# com.net
KiCad netlist of a schematic drawn in Altium Designer
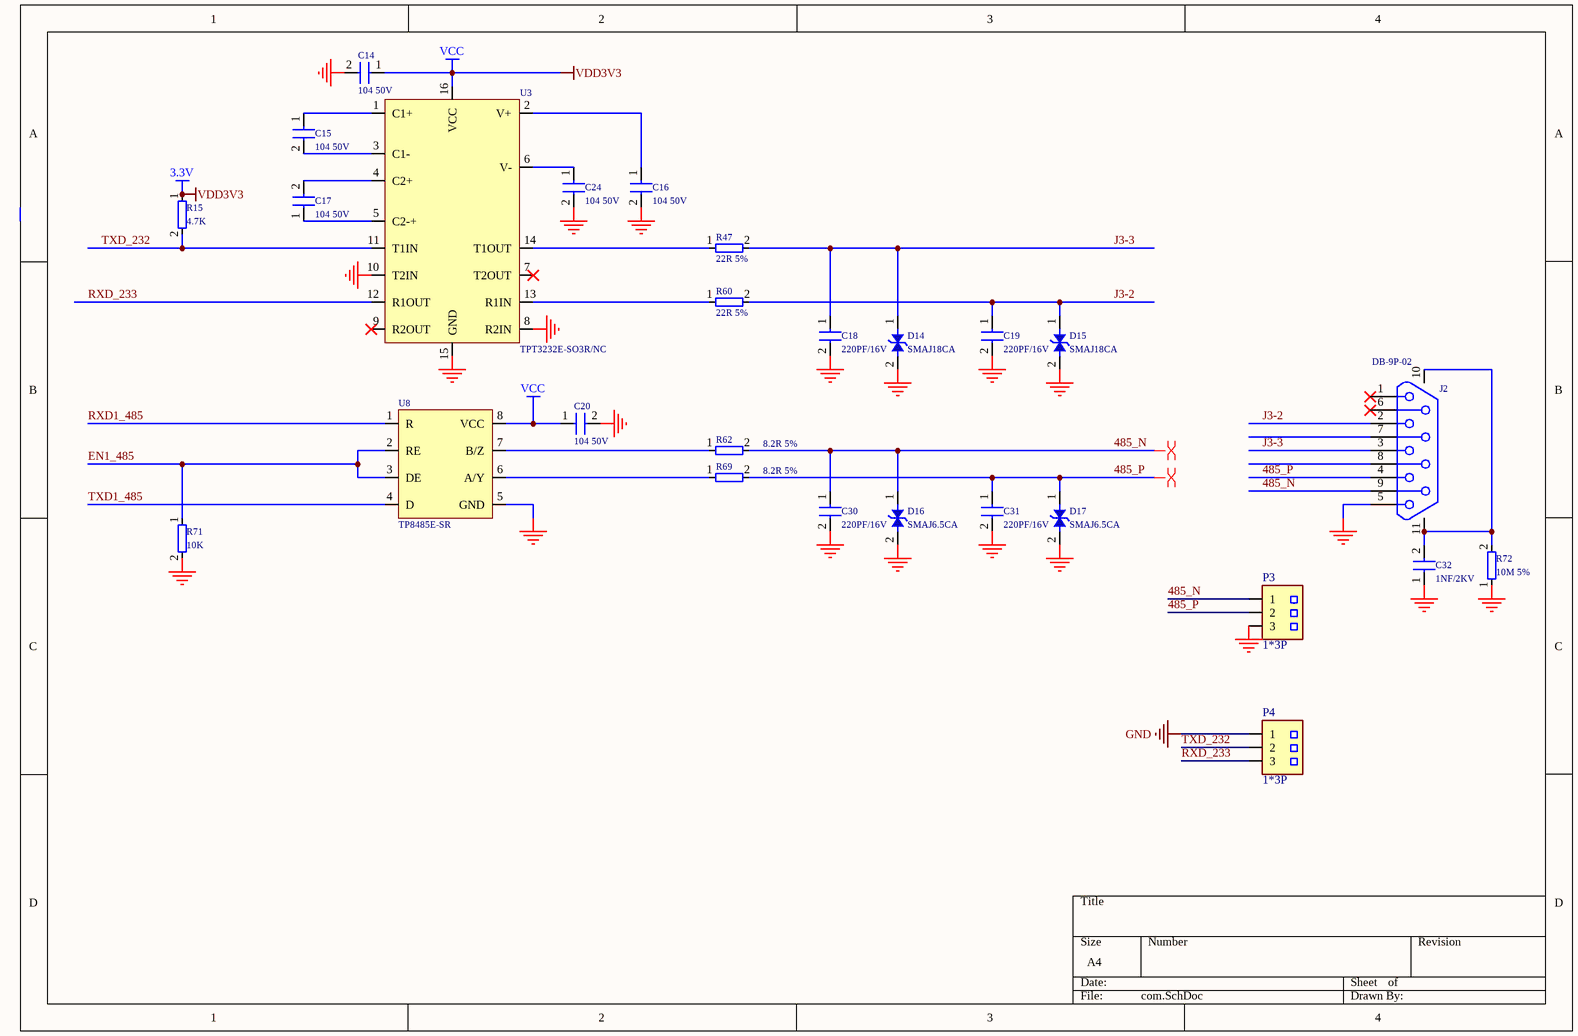
[diagram p0: com.SchDoc]

(export (version "E")
  (design (tool "Eeschema 10.0.6"))
  (components
    (comp (ref "C14") (value "104 50V") (footprint "0603C") (libsource (lib "*") (part "CAP")))
    (comp (ref "C15") (value "104 50V") (footprint "0603C") (libsource (lib "*") (part "CAP")))
    (comp (ref "C16") (value "104 50V") (footprint "0603C") (libsource (lib "*") (part "CAP")))
    (comp (ref "C17") (value "104 50V") (footprint "0603C") (libsource (lib "*") (part "CAP")))
    (comp (ref "C18") (value "220PF/16V") (footprint "0603C") (libsource (lib "*") (part "CAP")))
    (comp (ref "C19") (value "220PF/16V") (footprint "0603C") (libsource (lib "*") (part "CAP")))
    (comp (ref "C20") (value "104 50V") (footprint "0603C") (libsource (lib "*") (part "CAP")))
    (comp (ref "C24") (value "104 50V") (footprint "0603C") (libsource (lib "*") (part "CAP")))
    (comp (ref "C30") (value "220PF/16V") (footprint "0603C") (libsource (lib "*") (part "CAP")))
    (comp (ref "C31") (value "220PF/16V") (footprint "0603C") (libsource (lib "*") (part "CAP")))
    (comp (ref "C32") (value "1NF/2KV") (footprint "1206C") (libsource (lib "*") (part "CAP")))
    (comp (ref "D14") (value "SMAJ18CA") (footprint "SMA") (libsource (lib "*") (part "D_ESD")))
    (comp (ref "D15") (value "SMAJ18CA") (footprint "SMA") (libsource (lib "*") (part "D_ESD")))
    (comp (ref "D16") (value "SMAJ6.5CA") (footprint "SMA") (libsource (lib "*") (part "D_ESD")))
    (comp (ref "D17") (value "SMAJ6.5CA") (footprint "SMA") (libsource (lib "*") (part "D_ESD")))
    (comp (ref "J2") (value "DB-9P-02") (footprint "DIP-9") (libsource (lib "*") (part "DB9")))
    (comp (ref "P3") (value "1*3P") (footprint "3X2.54MMZ2") (libsource (lib "PARK-N5 V1.0") (part "HDR1*3")))
    (comp (ref "P4") (value "1*3P") (footprint "3X2.54MMZ2") (libsource (lib "PARK-N5 V1.0") (part "HDR1*3")))
    (comp (ref "R15") (value "4.7K") (footprint "0603R") (libsource (lib "*") (part "RES")))
    (comp (ref "R47") (value "22R 5%") (footprint "0603R") (libsource (lib "*") (part "RES")))
    (comp (ref "R60") (value "22R 5%") (footprint "0603R") (libsource (lib "*") (part "RES")))
    (comp (ref "R62") (value "8.2R 5%") (footprint "0603R") (libsource (lib "*") (part "RES")))
    (comp (ref "R69") (value "8.2R 5%") (footprint "0603R") (libsource (lib "*") (part "RES")))
    (comp (ref "R71") (value "10K") (footprint "0603R") (libsource (lib "*") (part "RES")))
    (comp (ref "R72") (value "10M 5%") (footprint "1206r") (libsource (lib "*") (part "RES")))
    (comp (ref "U3")
      (value "TPT3232E-SO3R/NC")
      (footprint "SO-16Z")
      (libsource (lib "*") (part "TPT3232E-SO3R"))
    )
    (comp (ref "U8") (value "TP8485E-SR") (footprint "SO-8") (libsource (lib "*") (part "TP8485E-SR")))
  )
  (nets
    (net (code "1") (name "/485_N") (class "Default")
      (node (ref "C30") (pin "1") (pintype "passive"))
      (node (ref "D16") (pin "1") (pintype "passive"))
      (node (ref "J2") (pin "9") (pinfunction "9_9") (pintype "passive"))
      (node (ref "P3") (pin "1") (pinfunction "1_1") (pintype "passive"))
      (node (ref "R62") (pin "2") (pinfunction "2_2") (pintype "passive"))
    )
    (net (code "2") (name "/485_P") (class "Default")
      (node (ref "C31") (pin "1") (pintype "passive"))
      (node (ref "D17") (pin "1") (pintype "passive"))
      (node (ref "J2") (pin "4") (pinfunction "4_4") (pintype "passive"))
      (node (ref "P3") (pin "2") (pinfunction "2_2") (pintype "passive"))
      (node (ref "R69") (pin "2") (pinfunction "2_2") (pintype "passive"))
    )
    (net (code "3") (name "/EN1_485") (class "Default")
      (node (ref "R71") (pin "1") (pinfunction "1_1") (pintype "passive"))
      (node (ref "U8") (pin "2") (pinfunction "RE_2") (pintype "passive"))
      (node (ref "U8") (pin "3") (pinfunction "DE_3") (pintype "passive"))
    )
    (net (code "4") (name "/J3-2") (class "Default")
      (node (ref "C19") (pin "1") (pintype "passive"))
      (node (ref "D15") (pin "1") (pintype "passive"))
      (node (ref "J2") (pin "2") (pinfunction "2_2") (pintype "passive"))
      (node (ref "R60") (pin "2") (pinfunction "2_2") (pintype "passive"))
    )
    (net (code "5") (name "/J3-3") (class "Default")
      (node (ref "C18") (pin "1") (pintype "passive"))
      (node (ref "D14") (pin "1") (pintype "passive"))
      (node (ref "J2") (pin "3") (pinfunction "3_3") (pintype "passive"))
      (node (ref "R47") (pin "2") (pinfunction "2_2") (pintype "passive"))
    )
    (net (code "6") (name "/RXD1_485") (class "Default")
      (node (ref "U8") (pin "1") (pinfunction "R_1") (pintype "passive"))
    )
    (net (code "7") (name "/RXD_233") (class "Default")
      (node (ref "P4") (pin "3") (pinfunction "3_3") (pintype "passive"))
      (node (ref "U3") (pin "12") (pinfunction "R1OUT_12") (pintype "passive"))
    )
    (net (code "8") (name "/TXD1_485") (class "Default")
      (node (ref "U8") (pin "4") (pinfunction "D_4") (pintype "passive"))
    )
    (net (code "9") (name "/TXD_232") (class "Default")
      (node (ref "P4") (pin "2") (pinfunction "2_2") (pintype "passive"))
      (node (ref "R15") (pin "2") (pinfunction "2_2") (pintype "passive"))
      (node (ref "U3") (pin "11") (pinfunction "T1IN_11") (pintype "passive"))
    )
    (net (code "10") (name "3.3V") (class "Default")
      (node (ref "C14") (pin "1") (pintype "passive"))
      (node (ref "C20") (pin "1") (pintype "passive"))
      (node (ref "R15") (pin "1") (pinfunction "1_1") (pintype "passive"))
      (node (ref "U3") (pin "16") (pinfunction "VCC_16") (pintype "passive"))
      (node (ref "U8") (pin "8") (pinfunction "VCC_8") (pintype "passive"))
    )
    (net (code "11") (name "GND") (class "Default")
      (node (ref "C14") (pin "2") (pintype "passive"))
      (node (ref "C16") (pin "2") (pintype "passive"))
      (node (ref "C18") (pin "2") (pintype "passive"))
      (node (ref "C19") (pin "2") (pintype "passive"))
      (node (ref "C20") (pin "2") (pintype "passive"))
      (node (ref "C24") (pin "2") (pintype "passive"))
      (node (ref "C30") (pin "2") (pintype "passive"))
      (node (ref "C31") (pin "2") (pintype "passive"))
      (node (ref "C32") (pin "1") (pintype "passive"))
      (node (ref "D14") (pin "2") (pintype "passive"))
      (node (ref "D15") (pin "2") (pintype "passive"))
      (node (ref "D16") (pin "2") (pintype "passive"))
      (node (ref "D17") (pin "2") (pintype "passive"))
      (node (ref "J2") (pin "5") (pinfunction "5_5") (pintype "passive"))
      (node (ref "P3") (pin "3") (pinfunction "3_3") (pintype "passive"))
      (node (ref "P4") (pin "1") (pinfunction "1_1") (pintype "passive"))
      (node (ref "R71") (pin "2") (pinfunction "2_2") (pintype "passive"))
      (node (ref "R72") (pin "1") (pinfunction "1_1") (pintype "passive"))
      (node (ref "U3") (pin "10") (pinfunction "T2IN_10") (pintype "passive"))
      (node (ref "U3") (pin "15") (pinfunction "GND_15") (pintype "passive"))
      (node (ref "U3") (pin "8") (pinfunction "R2IN_8") (pintype "passive"))
      (node (ref "U8") (pin "5") (pinfunction "GND_5") (pintype "passive"))
    )
    (net (code "12") (name "Net-(C32-Pad2)") (class "Default")
      (node (ref "C32") (pin "2") (pintype "passive"))
      (node (ref "J2") (pin "10") (pintype "passive"))
      (node (ref "J2") (pin "11") (pintype "passive"))
      (node (ref "R72") (pin "2") (pinfunction "2_2") (pintype "passive"))
    )
    (net (code "13") (name "Net-(U3-C1+)") (class "Default")
      (node (ref "C15") (pin "1") (pintype "passive"))
      (node (ref "U3") (pin "1") (pinfunction "C1+_1") (pintype "passive"))
    )
    (net (code "14") (name "Net-(U3-C1-)") (class "Default")
      (node (ref "C15") (pin "2") (pintype "passive"))
      (node (ref "U3") (pin "3") (pinfunction "C1-_3") (pintype "passive"))
    )
    (net (code "15") (name "Net-(U3-C2+)") (class "Default")
      (node (ref "C17") (pin "2") (pintype "passive"))
      (node (ref "U3") (pin "4") (pinfunction "C2+_4") (pintype "passive"))
    )
    (net (code "16") (name "Net-(U3-C2-+)") (class "Default")
      (node (ref "C17") (pin "1") (pintype "passive"))
      (node (ref "U3") (pin "5") (pinfunction "C2-+_5") (pintype "passive"))
    )
    (net (code "17") (name "Net-(U3-R1IN)") (class "Default")
      (node (ref "R60") (pin "1") (pinfunction "1_1") (pintype "passive"))
      (node (ref "U3") (pin "13") (pinfunction "R1IN_13") (pintype "passive"))
    )
    (net (code "18") (name "Net-(U3-T1OUT)") (class "Default")
      (node (ref "R47") (pin "1") (pinfunction "1_1") (pintype "passive"))
      (node (ref "U3") (pin "14") (pinfunction "T1OUT_14") (pintype "passive"))
    )
    (net (code "19") (name "Net-(U3-V+)") (class "Default")
      (node (ref "C16") (pin "1") (pintype "passive"))
      (node (ref "U3") (pin "2") (pinfunction "V+_2") (pintype "passive"))
    )
    (net (code "20") (name "Net-(U3-V-)") (class "Default")
      (node (ref "C24") (pin "1") (pintype "passive"))
      (node (ref "U3") (pin "6") (pinfunction "V-_6") (pintype "passive"))
    )
    (net (code "21") (name "Net-(U8-A{slash}Y)") (class "Default")
      (node (ref "R69") (pin "1") (pinfunction "1_1") (pintype "passive"))
      (node (ref "U8") (pin "6") (pinfunction "A/Y_6") (pintype "passive"))
    )
    (net (code "22") (name "Net-(U8-B{slash}Z)") (class "Default")
      (node (ref "R62") (pin "1") (pinfunction "1_1") (pintype "passive"))
      (node (ref "U8") (pin "7") (pinfunction "B/Z_7") (pintype "passive"))
    )
    (net (code "23") (name "unconnected-(J2-Pad1)") (class "Default")
      (node (ref "J2") (pin "1") (pinfunction "1_1") (pintype "passive+no_connect"))
    )
    (net (code "24") (name "unconnected-(J2-Pad6)") (class "Default")
      (node (ref "J2") (pin "6") (pinfunction "6_6") (pintype "passive+no_connect"))
    )
    (net (code "25") (name "unconnected-(J2-Pad7)") (class "Default")
      (node (ref "J2") (pin "7") (pinfunction "7_7") (pintype "passive"))
    )
    (net (code "26") (name "unconnected-(J2-Pad8)") (class "Default")
      (node (ref "J2") (pin "8") (pinfunction "8_8") (pintype "passive"))
    )
    (net (code "27") (name "unconnected-(U3-R2OUT-Pad9)") (class "Default")
      (node (ref "U3") (pin "9") (pinfunction "R2OUT_9") (pintype "passive+no_connect"))
    )
    (net (code "28") (name "unconnected-(U3-T2OUT-Pad7)") (class "Default")
      (node (ref "U3") (pin "7") (pinfunction "T2OUT_7") (pintype "passive+no_connect"))
    )
  )
)
